# Signal_generator.net
KiCad netlist of a schematic drawn in Altium Designer
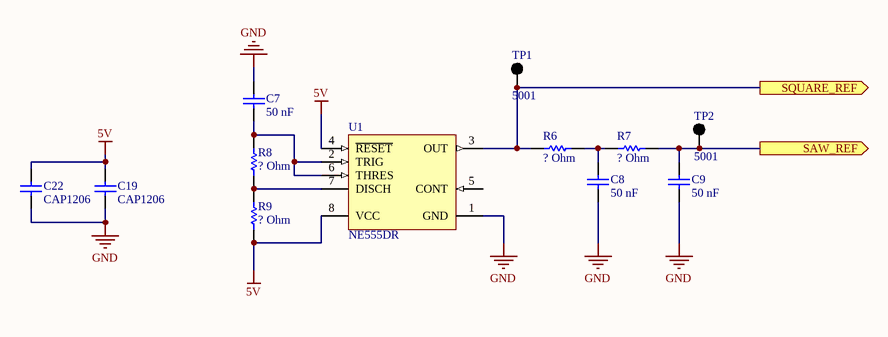
[diagram p0: Signal_generator.SchDoc]

(export (version "E")
  (design (tool "Eeschema 10.0.6"))
  (components
    (comp (ref "C7")
      (value "50 nF")
      (footprint "CAPC0805(2012)75_M")
      (description "CAP 0.5pF 50V ±0.1pF 0805 (2012 Metric) Thickness 0.75mm SMD")
      (fields (field (name "TOLERANCE") "Â±0.1pF"))
      (libsource (lib "Altium Content Vault") (part "CMP-1036-00018-1"))
    )
    (comp (ref "C8")
      (value "50 nF")
      (footprint "CAPC0805(2012)75_M")
      (description "CAP 0.5pF 50V ±0.1pF 0805 (2012 Metric) Thickness 0.75mm SMD")
      (fields (field (name "TOLERANCE") "Â±0.1pF"))
      (libsource (lib "Altium Content Vault") (part "CMP-1036-00018-1"))
    )
    (comp (ref "C9")
      (value "50 nF")
      (footprint "CAPC0805(2012)75_M")
      (description "CAP 0.5pF 50V ±0.1pF 0805 (2012 Metric) Thickness 0.75mm SMD")
      (fields (field (name "TOLERANCE") "Â±0.1pF"))
      (libsource (lib "Altium Content Vault") (part "CMP-1036-00018-1"))
    )
    (comp (ref "C19")
      (value "CAP1206")
      (footprint "CAPC1206(3216)150_L")
      (description "1206 (3216 Metric) Chip Capacitor")
      (libsource (lib "Altium Content Vault") (part "CAP_5"))
    )
    (comp (ref "C22")
      (value "CAP1206")
      (footprint "CAPC1206(3216)150_L")
      (description "1206 (3216 Metric) Chip Capacitor")
      (libsource (lib "Altium Content Vault") (part "CAP_5"))
    )
    (comp (ref "R6")
      (value "? Ohm")
      (footprint "RESC0805(2012)_M")
      (description "4R3 0.125W 5% 0805 (2012 Metric)  SMD")
      (fields (field (name "TOLERANCE") "5 %") (field (name "POWER") "0.125 W"))
      (libsource (lib "Altium Content Vault") (part "RES"))
    )
    (comp (ref "R7")
      (value "? Ohm")
      (footprint "RESC0805(2012)_M")
      (description "4R3 0.125W 5% 0805 (2012 Metric)  SMD")
      (fields (field (name "TOLERANCE") "5 %") (field (name "POWER") "0.125 W"))
      (libsource (lib "Altium Content Vault") (part "RES"))
    )
    (comp (ref "R8")
      (value "? Ohm")
      (footprint "RESC0805(2012)_M")
      (description "4R3 0.125W 5% 0805 (2012 Metric)  SMD")
      (fields (field (name "TOLERANCE") "5 %") (field (name "POWER") "0.125 W"))
      (libsource (lib "Altium Content Vault") (part "RES"))
    )
    (comp (ref "R9")
      (value "? Ohm")
      (footprint "RESC0805(2012)_M")
      (description "4R3 0.125W 5% 0805 (2012 Metric)  SMD")
      (fields (field (name "TOLERANCE") "5 %") (field (name "POWER") "0.125 W"))
      (libsource (lib "Altium Content Vault") (part "RES"))
    )
    (comp (ref "TP1")
      (value "5001")
      (footprint "KSTN-5001")
      (description "Test Point, Black, 1-Pin THD, RoHS, Bulk")
      (fields (field (name "MANUFACTURER") "Keystone"))
      (libsource (lib "Altium Content Vault") (part "KSTN-TP-5001"))
    )
    (comp (ref "TP2")
      (value "5001")
      (footprint "KSTN-5001")
      (description "Test Point, Black, 1-Pin THD, RoHS, Bulk")
      (fields (field (name "MANUFACTURER") "Keystone"))
      (libsource (lib "Altium Content Vault") (part "KSTN-TP-5001"))
    )
    (comp (ref "U1")
      (value "NE555DR")
      (footprint "D0008A_M")
      (libsource (lib "Altium Content Vault") (part "TI-NE555-P8"))
    )
  )
  (nets
    (net (code "1") (name "/SAW_REF") (class "Default")
      (node (ref "C9") (pin "1") (pinfunction "1_1") (pintype "passive"))
      (node (ref "R7") (pin "2") (pinfunction "2_2") (pintype "passive"))
      (node (ref "TP2") (pin "1") (pintype "passive"))
    )
    (net (code "2") (name "/SQUARE_REF") (class "Default")
      (node (ref "R6") (pin "1") (pinfunction "1_1") (pintype "passive"))
      (node (ref "TP1") (pin "1") (pintype "passive"))
      (node (ref "U1") (pin "3") (pinfunction "OUT_3") (pintype "output"))
    )
    (net (code "3") (name "5V") (class "Default")
      (node (ref "C19") (pin "2") (pinfunction "2_2") (pintype "passive"))
      (node (ref "C22") (pin "2") (pinfunction "2_2") (pintype "passive"))
      (node (ref "R9") (pin "2") (pinfunction "2_2") (pintype "passive"))
      (node (ref "U1") (pin "4") (pinfunction "~{RESET}_4") (pintype "input"))
      (node (ref "U1") (pin "8") (pinfunction "VCC_8") (pintype "power_in"))
    )
    (net (code "4") (name "GND") (class "Default")
      (node (ref "C19") (pin "1") (pinfunction "1_1") (pintype "passive"))
      (node (ref "C22") (pin "1") (pinfunction "1_1") (pintype "passive"))
      (node (ref "C7") (pin "1") (pinfunction "1_1") (pintype "passive"))
      (node (ref "C8") (pin "2") (pinfunction "2_2") (pintype "passive"))
      (node (ref "C9") (pin "2") (pinfunction "2_2") (pintype "passive"))
      (node (ref "U1") (pin "1") (pinfunction "GND_1") (pintype "power_in"))
    )
    (net (code "5") (name "Net-(C8-Pad1)") (class "Default")
      (node (ref "C8") (pin "1") (pinfunction "1_1") (pintype "passive"))
      (node (ref "R6") (pin "2") (pinfunction "2_2") (pintype "passive"))
      (node (ref "R7") (pin "1") (pinfunction "1_1") (pintype "passive"))
    )
    (net (code "6") (name "Net-(U1-DISCH)") (class "Default")
      (node (ref "R8") (pin "2") (pinfunction "2_2") (pintype "passive"))
      (node (ref "R9") (pin "1") (pinfunction "1_1") (pintype "passive"))
      (node (ref "U1") (pin "7") (pinfunction "DISCH_7") (pintype "open_collector"))
    )
    (net (code "7") (name "Net-(U1-THRES)") (class "Default")
      (node (ref "C7") (pin "2") (pinfunction "2_2") (pintype "passive"))
      (node (ref "R8") (pin "1") (pinfunction "1_1") (pintype "passive"))
      (node (ref "U1") (pin "2") (pinfunction "TRIG_2") (pintype "input"))
      (node (ref "U1") (pin "6") (pinfunction "THRES_6") (pintype "input"))
    )
    (net (code "8") (name "unconnected-(U1-CONT-Pad5)") (class "Default")
      (node (ref "U1") (pin "5") (pinfunction "CONT_5") (pintype "input"))
    )
  )
)
